# SCH_Hack-Card_2025-02-01.net
KiCad netlist of a schematic drawn in EasyEDA
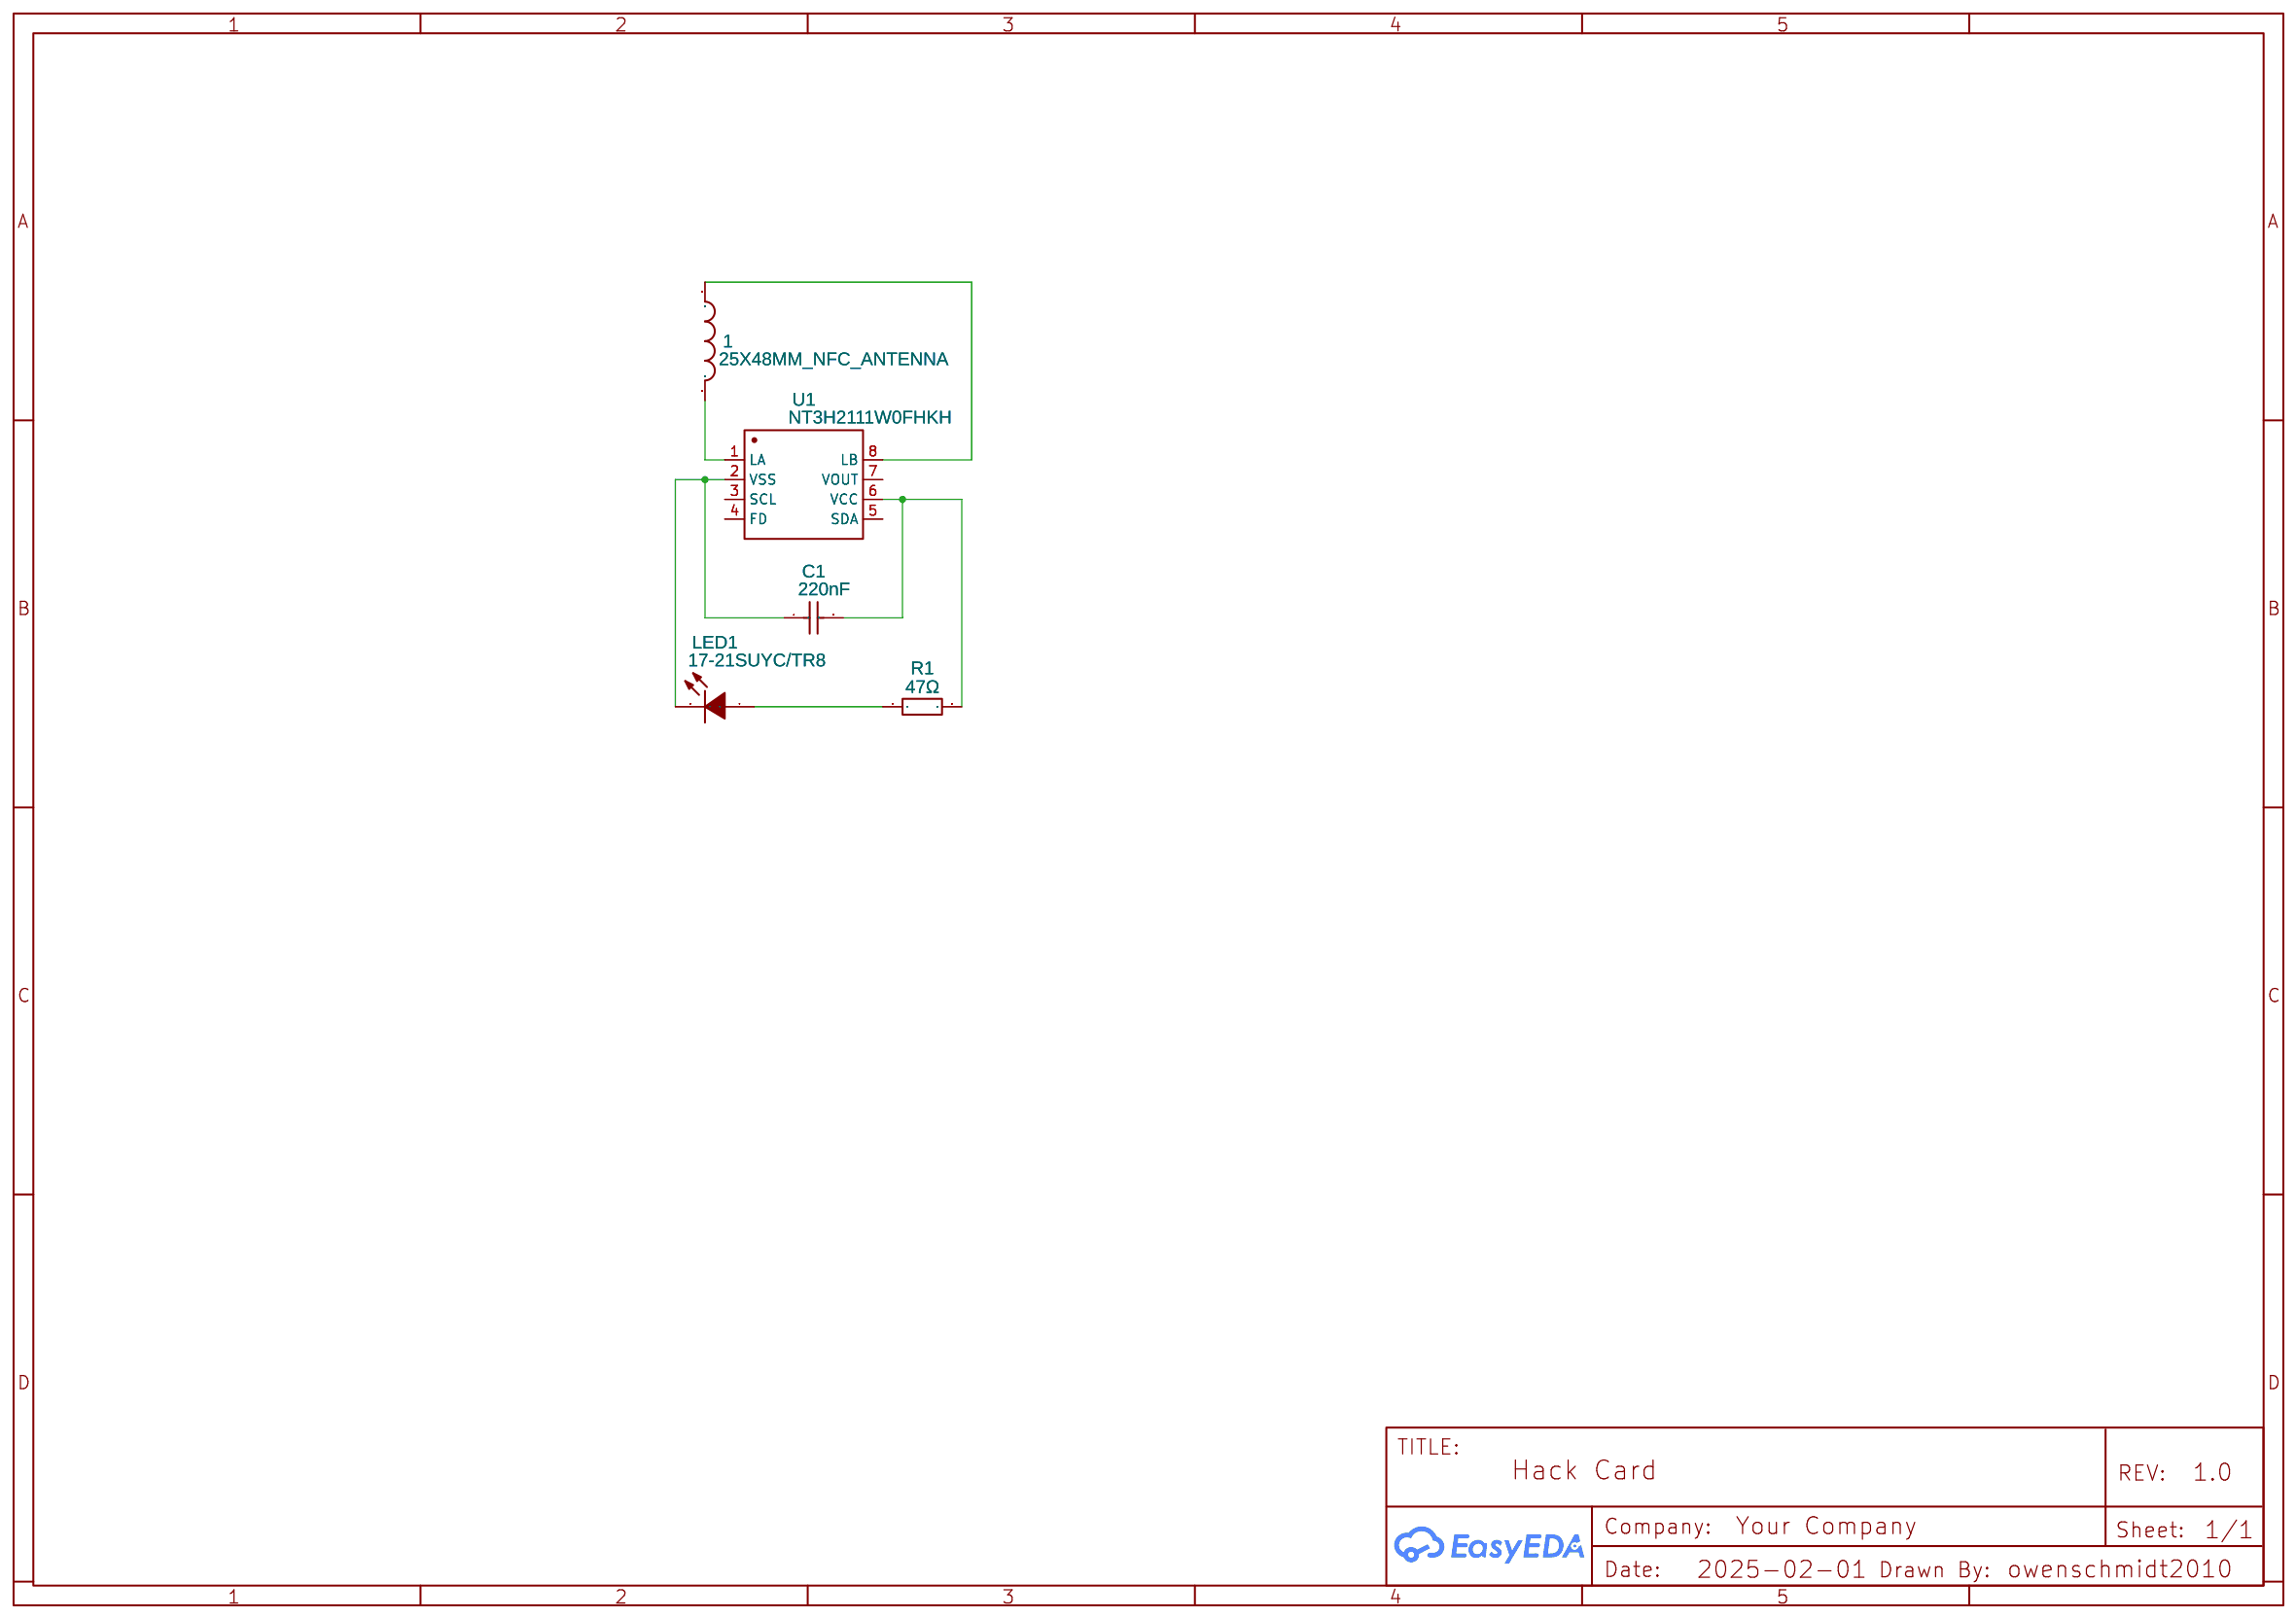
[diagram p0: schematic sheet]

(export (version "E")
  (design (tool "Eeschema 10.0.6"))
  (components
    (comp (ref "1") (value "25X48MM_NFC_ANTENNA") (libsource (lib "") (part "25X48MM_NFC_ANTENNA")))
    (comp (ref "C1")
      (value "220nF")
      (fields
        (field (name "Manufacturer Part") "CL10B224KA8NNNC")
        (field (name "Manufacturer") "SAMSUNG(三星)")
      )
      (libsource (lib "") (part "CL10B224KA8NNNC"))
    )
    (comp (ref "LED1")
      (value "17-21SUYC/TR8")
      (fields (field (name "Manufacturer Part") "KT-0805黄灯") (field (name "Manufacturer") "KENTO"))
      (libsource (lib "") (part "17-21SUYC/TR8"))
    )
    (comp (ref "R1")
      (value "47Ω")
      (fields
        (field (name "Manufacturer Part") "0603WAF470JT5E")
        (field (name "Manufacturer") "UNI-ROYAL(厚声)")
      )
      (libsource (lib "") (part "0603WAF470JT5E"))
    )
    (comp (ref "U1")
      (value "NT3H2111W0FHKH")
      (fields (field (name "Manufacturer") "NXP(恩智浦)"))
      (libsource (lib "") (part "NT3H2111W0FHKH"))
    )
  )
  (nets
    (net (code "1") (name "Net-(LED1-+)") (class "Default")
      (node (ref "LED1") (pin "1") (pinfunction "+_1") (pintype "unspecified"))
      (node (ref "R1") (pin "1") (pinfunction "1_1") (pintype "input"))
    )
    (net (code "2") (name "Net-(LED1--)") (class "Default")
      (node (ref "C1") (pin "1") (pinfunction "1_1") (pintype "input"))
      (node (ref "LED1") (pin "2") (pinfunction "-_2") (pintype "unspecified"))
      (node (ref "U1") (pin "2") (pinfunction "VSS_2") (pintype "unspecified"))
    )
    (net (code "3") (name "Net-(U1-LA)") (class "Default")
      (node (ref "1") (pin "P$2") (pinfunction "P$2_P$2") (pintype "bidirectional"))
      (node (ref "U1") (pin "1") (pinfunction "LA_1") (pintype "unspecified"))
    )
    (net (code "4") (name "Net-(U1-LB)") (class "Default")
      (node (ref "1") (pin "P$1") (pinfunction "P$1_P$1") (pintype "bidirectional"))
      (node (ref "U1") (pin "8") (pinfunction "LB_8") (pintype "unspecified"))
    )
    (net (code "5") (name "Net-(U1-VCC)") (class "Default")
      (node (ref "C1") (pin "2") (pinfunction "2_2") (pintype "input"))
      (node (ref "R1") (pin "2") (pinfunction "2_2") (pintype "input"))
      (node (ref "U1") (pin "6") (pinfunction "VCC_6") (pintype "unspecified"))
    )
    (net (code "6") (name "unconnected-(U1-FD-Pad4)") (class "Default")
      (node (ref "U1") (pin "4") (pinfunction "FD_4") (pintype "unspecified"))
    )
    (net (code "7") (name "unconnected-(U1-SCL-Pad3)") (class "Default")
      (node (ref "U1") (pin "3") (pinfunction "SCL_3") (pintype "unspecified"))
    )
    (net (code "8") (name "unconnected-(U1-SDA-Pad5)") (class "Default")
      (node (ref "U1") (pin "5") (pinfunction "SDA_5") (pintype "unspecified"))
    )
    (net (code "9") (name "unconnected-(U1-VOUT-Pad7)") (class "Default")
      (node (ref "U1") (pin "7") (pinfunction "VOUT_7") (pintype "unspecified"))
    )
  )
)
